# NRF.net
KiCad netlist of a schematic drawn in Altium Designer
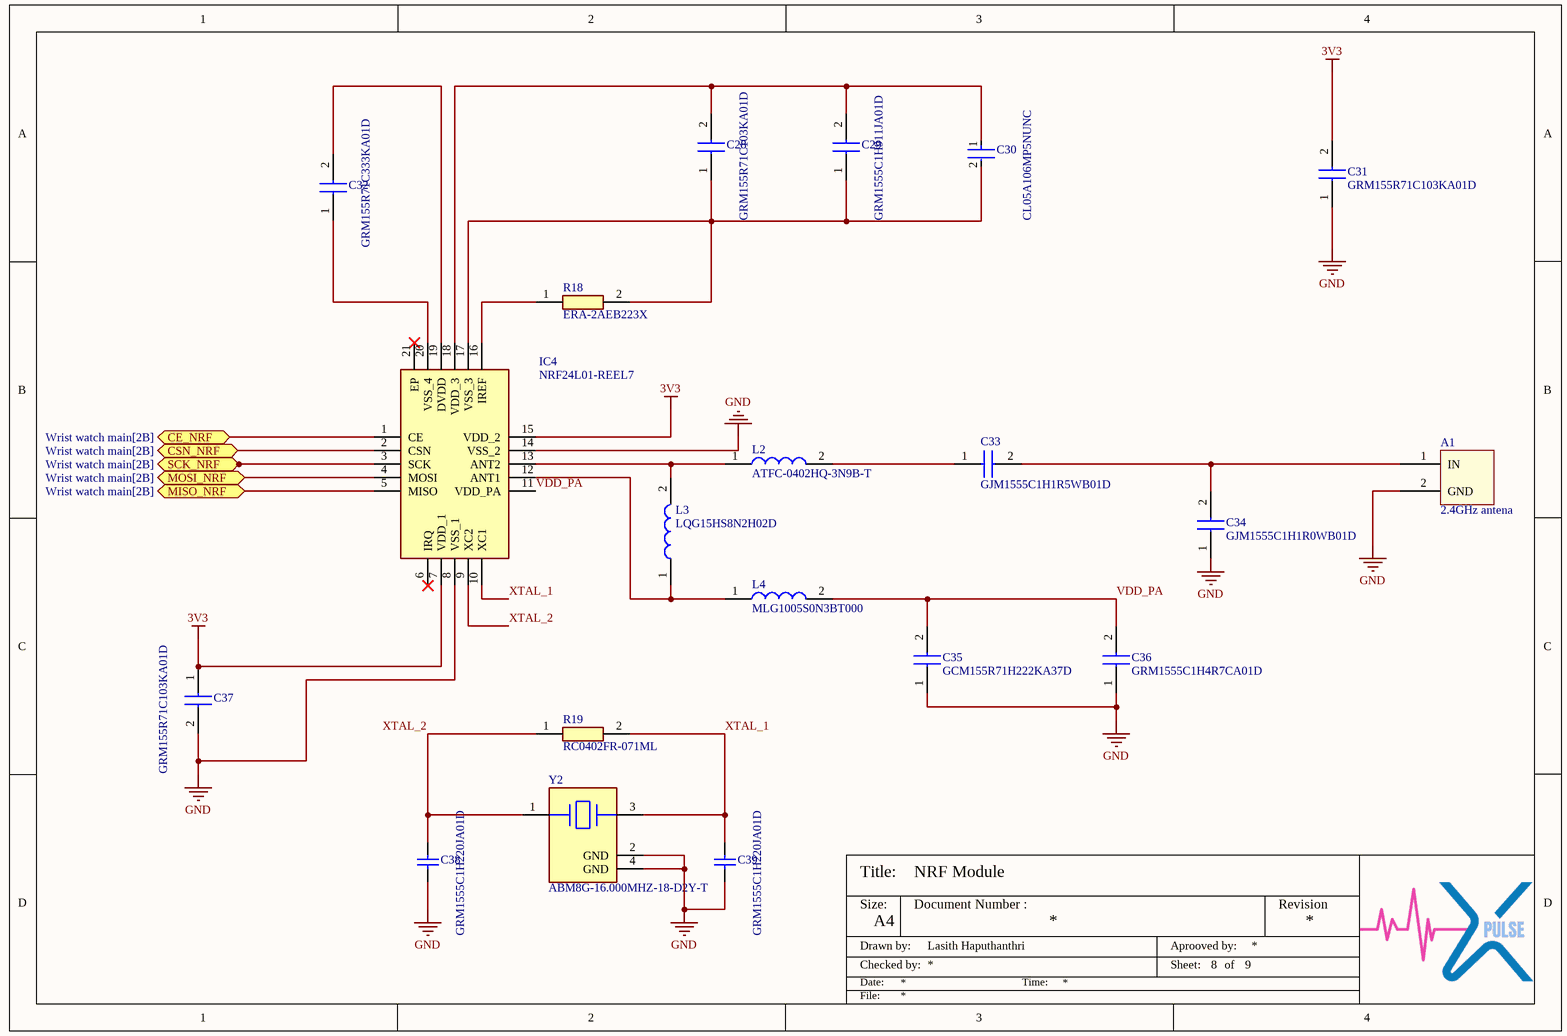
[diagram p0: NRF.SchDoc]

(export (version "E")
  (design (tool "Eeschema 10.0.6"))
  (components
    (comp (ref "A1")
      (value "2.4GHz antena")
      (footprint "Antena")
      (libsource (lib "My Components") (part "2.4GHz antena"))
    )
    (comp (ref "C28")
      (value "GRM155R71C103KA01D")
      (footprint "SamacSys:CAPC1005X55N")
      (description "Capacitor")
      (fields (field (name "MOUSER PART NUMBER") "81-GRM36X103K16"))
      (libsource (lib "*") (part "GRM155R71C103KA01D"))
    )
    (comp (ref "C29")
      (value "GRM1555C1H911JA01D")
      (footprint "SamacSys:CAPC1005X55N")
      (description "Capacitor")
      (fields (field (name "MOUSER PART NUMBER") "81-GRM1555C1H911JA1D"))
      (libsource (lib "*") (part "GRM1555C1H911JA01D"))
    )
    (comp (ref "C30")
      (value "CL05A106MP5NUNC")
      (footprint "FP-CL05A106MP5NUNC-MFG")
      (description "CAP CER 10UF 10V X5R 0402")
      (fields
        (field (name "OCTOPART") "https://octopart.com/cl05a106mp5nunc-samsung-22457395")
        (field (name "TOLERANCE") "20%")
      )
      (libsource (lib "Altium Content Vault") (part "b4654b650e69147ec39a6b967a45e02"))
    )
    (comp (ref "C31")
      (value "GRM155R71C103KA01D")
      (footprint "SamacSys:CAPC1005X55N")
      (description "Capacitor")
      (fields (field (name "MOUSER PART NUMBER") "81-GRM36X103K16"))
      (libsource (lib "*") (part "GRM155R71C103KA01D"))
    )
    (comp (ref "C32")
      (value "GRM155R71C333KA01D")
      (footprint "SamacSys:CAPC1005X55N")
      (description "Capacitor")
      (libsource (lib "*") (part "GRM155R71C333KA01D"))
    )
    (comp (ref "C33")
      (value "GJM1555C1H1R5WB01D")
      (footprint "SamacSys:CAPC1005X55N")
      (description "Capacitor")
      (fields (field (name "MOUSER PART NUMBER") "81-GJM1555C1H1R5WB1D"))
      (libsource (lib "*") (part "GJM1555C1H1R5WB01D"))
    )
    (comp (ref "C34")
      (value "GJM1555C1H1R0WB01D")
      (footprint "SamacSys:CAPC1005X55N")
      (description "Capacitor")
      (fields (field (name "MOUSER PART NUMBER") "81-GJM1555C1H1R0WB1D"))
      (libsource (lib "*") (part "GJM1555C1H1R0WB01D"))
    )
    (comp (ref "C35")
      (value "GCM155R71H222KA37D")
      (footprint "SamacSys:CAPC1005X55N")
      (description "Capacitor")
      (fields (field (name "MOUSER PART NUMBER") "81-GCM155R71H222K37D"))
      (libsource (lib "*") (part "GCM155R71H222KA37D"))
    )
    (comp (ref "C36")
      (value "GRM1555C1H4R7CA01D")
      (footprint "SamacSys:CAPC1005X55N")
      (description "Capacitor")
      (fields (field (name "MOUSER PART NUMBER") "81-GRM1555C1H4R7CA1D"))
      (libsource (lib "*") (part "GRM1555C1H4R7CA01D"))
    )
    (comp (ref "C37")
      (value "GRM155R71C103KA01D")
      (footprint "SamacSys:CAPC1005X55N")
      (description "Capacitor")
      (fields (field (name "MOUSER PART NUMBER") "81-GRM36X103K16"))
      (libsource (lib "*") (part "GRM155R71C103KA01D"))
    )
    (comp (ref "C38")
      (value "GRM1555C1H220JA01D")
      (footprint "CAPC1005X55X25NL05T10")
      (fields (field (name "MANUFACTURER") "Murata"))
      (libsource (lib "Altium Content Vault") (part "CAP"))
    )
    (comp (ref "C39")
      (value "GRM1555C1H220JA01D")
      (footprint "CAPC1005X55X25NL05T10")
      (fields (field (name "MANUFACTURER") "Murata"))
      (libsource (lib "Altium Content Vault") (part "CAP"))
    )
    (comp (ref "IC4")
      (value "NRF24L01-REEL7")
      (footprint "SamacSys:QFN50P400X400X80-21N-D")
      (description "Integrated Circuit")
      (fields (field (name "MOUSER PART NUMBER") "949-NRF24L01-REEL7"))
      (libsource (lib "*") (part "NRF24L01-REEL7"))
    )
    (comp (ref "L2")
      (value "ATFC-0402HQ-3N9B-T")
      (footprint "SamacSys:INDC1005X37N")
      (description "Inductor")
      (libsource (lib "*") (part "ATFC-0402HQ-3N9B-T"))
    )
    (comp (ref "L3")
      (value "LQG15HS8N2H02D")
      (footprint "SamacSys:LQG15WH0N7B02D")
      (description "Inductor")
      (fields (field (name "MOUSER PART NUMBER") "81-LQG15HS8N2H02D"))
      (libsource (lib "*") (part "LQG15HS8N2H02D"))
    )
    (comp (ref "L4")
      (value "MLG1005S0N3BT000")
      (footprint "SamacSys:MLG1005")
      (description "Inductor")
      (fields (field (name "MOUSER PART NUMBER") "810-MLG1005S0N3BT000"))
      (libsource (lib "*") (part "MLG1005S0N3BT000"))
    )
    (comp (ref "R18")
      (value "ERA-2AEB223X")
      (footprint "SamacSys:ERA2AED122X")
      (description "Resistor")
      (fields (field (name "MOUSER PART NUMBER") "667-ERA-2AEB223X"))
      (libsource (lib "*") (part "ERA-2AEB223X"))
    )
    (comp (ref "R19")
      (value "RC0402FR-071ML")
      (footprint "SamacSys:RESC1005X40N")
      (description "Resistor")
      (fields (field (name "MOUSER PART NUMBER") "603-RC0402FR-071ML"))
      (libsource (lib "*") (part "RC0402FR-071ML"))
    )
    (comp (ref "Y2")
      (value "ABM8G-16.000MHZ-18-D2Y-T")
      (footprint "FP-ABM8G-MFG")
      (description "Crystal 12MHz ±20ppm (Tol) ±30ppm (Stability) 18pF FUND 120Ω 4-Pin SMD T/R")
      (fields (field (name "TOLERANCE") "20ppm"))
      (libsource (lib "Altium Content Vault") (part "48e526d86b7f2615d98721063c72f49"))
    )
  )
  (nets
    (net (code "1") (name "/CE_NRF") (class "Default")
      (node (ref "IC4") (pin "1") (pinfunction "CE_1") (pintype "passive"))
    )
    (net (code "2") (name "/CSN_NRF") (class "Default")
      (node (ref "IC4") (pin "2") (pinfunction "CSN_2") (pintype "passive"))
    )
    (net (code "3") (name "/MISO_NRF") (class "Default")
      (node (ref "IC4") (pin "5") (pinfunction "MISO_5") (pintype "passive"))
    )
    (net (code "4") (name "/MOSI_NRF") (class "Default")
      (node (ref "IC4") (pin "4") (pinfunction "MOSI_4") (pintype "passive"))
    )
    (net (code "5") (name "/SCK_NRF") (class "Default")
      (node (ref "IC4") (pin "3") (pinfunction "SCK_3") (pintype "passive"))
    )
    (net (code "6") (name "/VDD_PA") (class "Default")
      (node (ref "C35") (pin "2") (pinfunction "2_2") (pintype "passive"))
      (node (ref "C36") (pin "2") (pinfunction "2_2") (pintype "passive"))
      (node (ref "IC4") (pin "11") (pinfunction "VDD_PA_11") (pintype "passive"))
      (node (ref "L4") (pin "2") (pinfunction "2_2") (pintype "passive"))
    )
    (net (code "7") (name "/XTAL_1") (class "Default")
      (node (ref "C39") (pin "2") (pinfunction "2_2") (pintype "passive"))
      (node (ref "IC4") (pin "10") (pinfunction "XC1_10") (pintype "passive"))
      (node (ref "R19") (pin "2") (pinfunction "2_2") (pintype "passive"))
      (node (ref "Y2") (pin "3") (pinfunction "3_3") (pintype "passive"))
    )
    (net (code "8") (name "/XTAL_2") (class "Default")
      (node (ref "C38") (pin "2") (pinfunction "2_2") (pintype "passive"))
      (node (ref "IC4") (pin "9") (pinfunction "XC2_9") (pintype "passive"))
      (node (ref "R19") (pin "1") (pinfunction "1_1") (pintype "passive"))
      (node (ref "Y2") (pin "1") (pinfunction "1_1") (pintype "passive"))
    )
    (net (code "9") (name "3V3") (class "Default")
      (node (ref "C31") (pin "2") (pinfunction "2_2") (pintype "passive"))
      (node (ref "C37") (pin "1") (pinfunction "1_1") (pintype "passive"))
      (node (ref "IC4") (pin "15") (pinfunction "VDD_2_15") (pintype "passive"))
      (node (ref "IC4") (pin "7") (pinfunction "VDD_1_7") (pintype "passive"))
    )
    (net (code "10") (name "GND") (class "Default")
      (node (ref "A1") (pin "2") (pinfunction "GND_2") (pintype "passive"))
      (node (ref "C31") (pin "1") (pinfunction "1_1") (pintype "passive"))
      (node (ref "C34") (pin "1") (pinfunction "1_1") (pintype "passive"))
      (node (ref "C35") (pin "1") (pinfunction "1_1") (pintype "passive"))
      (node (ref "C36") (pin "1") (pinfunction "1_1") (pintype "passive"))
      (node (ref "C37") (pin "2") (pinfunction "2_2") (pintype "passive"))
      (node (ref "C38") (pin "1") (pinfunction "1_1") (pintype "passive"))
      (node (ref "C39") (pin "1") (pinfunction "1_1") (pintype "passive"))
      (node (ref "IC4") (pin "14") (pinfunction "VSS_2_14") (pintype "passive"))
      (node (ref "IC4") (pin "8") (pinfunction "VSS_1_8") (pintype "passive"))
      (node (ref "Y2") (pin "2") (pinfunction "GND_2") (pintype "power_in"))
      (node (ref "Y2") (pin "4") (pinfunction "GND_4") (pintype "power_in"))
    )
    (net (code "11") (name "Net-(A1-IN)") (class "Default")
      (node (ref "A1") (pin "1") (pinfunction "IN_1") (pintype "passive"))
      (node (ref "C33") (pin "2") (pinfunction "2_2") (pintype "passive"))
      (node (ref "C34") (pin "2") (pinfunction "2_2") (pintype "passive"))
    )
    (net (code "12") (name "Net-(C33-Pad1)") (class "Default")
      (node (ref "C33") (pin "1") (pinfunction "1_1") (pintype "passive"))
      (node (ref "L2") (pin "2") (pinfunction "2_2") (pintype "passive"))
    )
    (net (code "13") (name "Net-(IC4-ANT1)") (class "Default")
      (node (ref "IC4") (pin "12") (pinfunction "ANT1_12") (pintype "passive"))
      (node (ref "L3") (pin "1") (pinfunction "1_1") (pintype "passive"))
      (node (ref "L4") (pin "1") (pinfunction "1_1") (pintype "passive"))
    )
    (net (code "14") (name "Net-(IC4-ANT2)") (class "Default")
      (node (ref "IC4") (pin "13") (pinfunction "ANT2_13") (pintype "passive"))
      (node (ref "L2") (pin "1") (pinfunction "1_1") (pintype "passive"))
      (node (ref "L3") (pin "2") (pinfunction "2_2") (pintype "passive"))
    )
    (net (code "15") (name "Net-(IC4-DVDD)") (class "Default")
      (node (ref "C32") (pin "2") (pinfunction "2_2") (pintype "passive"))
      (node (ref "IC4") (pin "19") (pinfunction "DVDD_19") (pintype "passive"))
    )
    (net (code "16") (name "Net-(IC4-IREF)") (class "Default")
      (node (ref "IC4") (pin "16") (pinfunction "IREF_16") (pintype "passive"))
      (node (ref "R18") (pin "1") (pinfunction "1_1") (pintype "passive"))
    )
    (net (code "17") (name "Net-(IC4-VDD_3)") (class "Default")
      (node (ref "C28") (pin "2") (pinfunction "2_2") (pintype "passive"))
      (node (ref "C29") (pin "2") (pinfunction "2_2") (pintype "passive"))
      (node (ref "C30") (pin "1") (pinfunction "1_1") (pintype "passive"))
      (node (ref "IC4") (pin "18") (pinfunction "VDD_3_18") (pintype "passive"))
    )
    (net (code "18") (name "Net-(IC4-VSS_3)") (class "Default")
      (node (ref "C28") (pin "1") (pinfunction "1_1") (pintype "passive"))
      (node (ref "C29") (pin "1") (pinfunction "1_1") (pintype "passive"))
      (node (ref "C30") (pin "2") (pinfunction "2_2") (pintype "passive"))
      (node (ref "IC4") (pin "17") (pinfunction "VSS_3_17") (pintype "passive"))
      (node (ref "R18") (pin "2") (pinfunction "2_2") (pintype "passive"))
    )
    (net (code "19") (name "Net-(IC4-VSS_4)") (class "Default")
      (node (ref "C32") (pin "1") (pinfunction "1_1") (pintype "passive"))
      (node (ref "IC4") (pin "20") (pinfunction "VSS_4_20") (pintype "passive"))
    )
    (net (code "20") (name "unconnected-(IC4-EP-Pad21)") (class "Default")
      (node (ref "IC4") (pin "21") (pinfunction "EP_21") (pintype "passive+no_connect"))
    )
    (net (code "21") (name "unconnected-(IC4-IRQ-Pad6)") (class "Default")
      (node (ref "IC4") (pin "6") (pinfunction "IRQ_6") (pintype "passive+no_connect"))
    )
  )
)
